# eBox_ACdetect2.net
KiCad netlist of a schematic drawn in Altium Designer
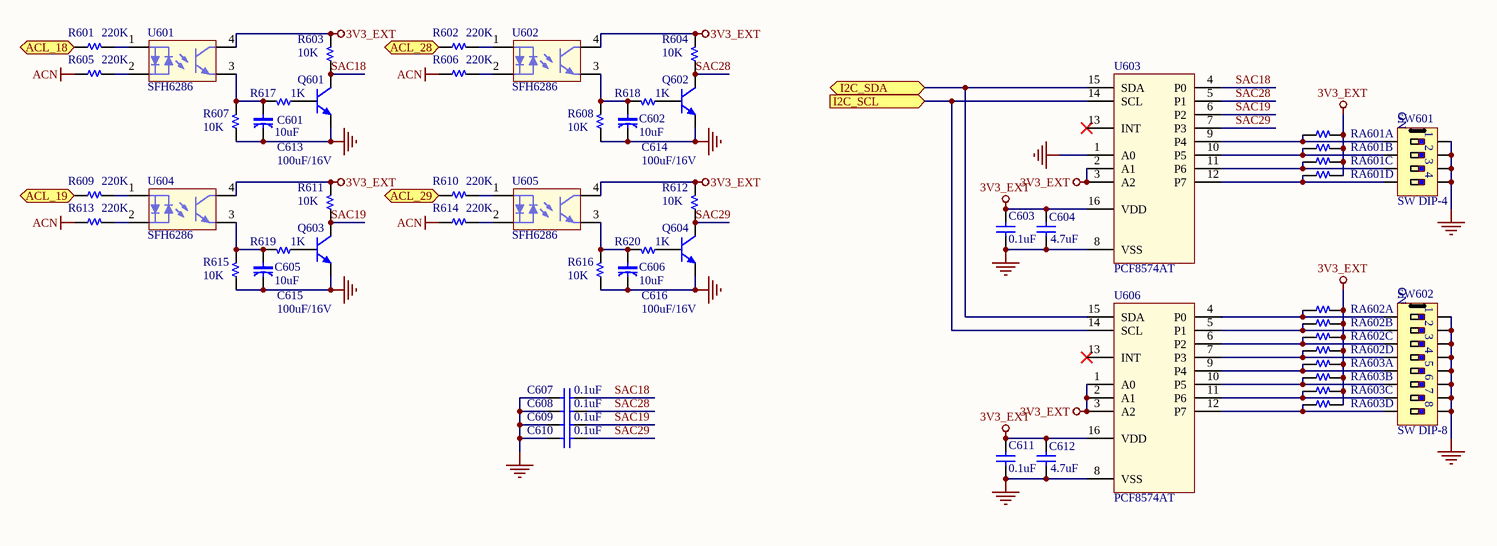
[diagram p0: eBox_ACdetect2.SchDoc]

(export (version "E")
  (design (tool "Eeschema 10.0.6"))
  (components
    (comp (ref "C601")
      (value "10uF")
      (footprint "C 0805")
      (description "CAP CER 0.1UF 50V X7R 0805")
      (libsource (lib "chipfc_altium_libs") (part "Capacitor NP"))
    )
    (comp (ref "C602")
      (value "10uF")
      (footprint "C 0805")
      (description "CAP CER 0.1UF 50V X7R 0805")
      (libsource (lib "chipfc_altium_libs") (part "Capacitor NP"))
    )
    (comp (ref "C603")
      (value "0.1uF")
      (footprint "C 0603")
      (description "CAP CER 0.1UF 50V X7R 0603")
      (libsource (lib "chipfc_altium_libs") (part "Capacitor NP"))
    )
    (comp (ref "C604")
      (value "4.7uF")
      (footprint "C 0603")
      (description "CAP CER 4.7UF 50V X7R 0603")
      (libsource (lib "chipfc_altium_libs") (part "Capacitor NP"))
    )
    (comp (ref "C605")
      (value "10uF")
      (footprint "C 0805")
      (description "CAP CER 0.1UF 50V X7R 0805")
      (libsource (lib "chipfc_altium_libs") (part "Capacitor NP"))
    )
    (comp (ref "C606")
      (value "10uF")
      (footprint "C 0805")
      (description "CAP CER 0.1UF 50V X7R 0805")
      (libsource (lib "chipfc_altium_libs") (part "Capacitor NP"))
    )
    (comp (ref "C607")
      (value "0.1uF")
      (footprint "C 0805")
      (description "CAP CER 0.1UF 50V X7R 0805")
      (libsource (lib "chipfc_altium_libs") (part "Capacitor NP"))
    )
    (comp (ref "C608")
      (value "0.1uF")
      (footprint "C 0805")
      (description "CAP CER 0.1UF 50V X7R 0805")
      (libsource (lib "chipfc_altium_libs") (part "Capacitor NP"))
    )
    (comp (ref "C609")
      (value "0.1uF")
      (footprint "C 0805")
      (description "CAP CER 0.1UF 50V X7R 0805")
      (libsource (lib "chipfc_altium_libs") (part "Capacitor NP"))
    )
    (comp (ref "C610")
      (value "0.1uF")
      (footprint "C 0805")
      (description "CAP CER 0.1UF 50V X7R 0805")
      (libsource (lib "chipfc_altium_libs") (part "Capacitor NP"))
    )
    (comp (ref "C611")
      (value "0.1uF")
      (footprint "C 0603")
      (description "CAP CER 0.1UF 50V X7R 0603")
      (libsource (lib "chipfc_altium_libs") (part "Capacitor NP"))
    )
    (comp (ref "C612")
      (value "4.7uF")
      (footprint "C 0603")
      (description "CAP CER 4.7UF 50V X7R 0603")
      (libsource (lib "chipfc_altium_libs") (part "Capacitor NP"))
    )
    (comp (ref "C613")
      (value "100uF/16V")
      (footprint "CYL/D.200/LS.75")
      (description "Capacitor pol")
      (libsource (lib "chipfc_altium_libs") (part "Capacitor"))
    )
    (comp (ref "C614")
      (value "100uF/16V")
      (footprint "CYL/D.200/LS.75")
      (description "Capacitor pol")
      (libsource (lib "chipfc_altium_libs") (part "Capacitor"))
    )
    (comp (ref "C615")
      (value "100uF/16V")
      (footprint "CYL/D.200/LS.75")
      (description "Capacitor pol")
      (libsource (lib "chipfc_altium_libs") (part "Capacitor"))
    )
    (comp (ref "C616")
      (value "100uF/16V")
      (footprint "CYL/D.200/LS.75")
      (description "Capacitor pol")
      (libsource (lib "chipfc_altium_libs") (part "Capacitor"))
    )
    (comp (ref "Q601")
      (value "MMBT3904LT1G")
      (footprint "SOT-23")
      (description "TRANS NPN 40V 0.2A SOT23")
      (libsource (lib "chipfc_altium_libs") (part "Transistor NPN"))
    )
    (comp (ref "Q602")
      (value "MMBT3904LT1G")
      (footprint "SOT-23")
      (description "TRANS NPN 40V 0.2A SOT23")
      (libsource (lib "chipfc_altium_libs") (part "Transistor NPN"))
    )
    (comp (ref "Q603")
      (value "MMBT3904LT1G")
      (footprint "SOT-23")
      (description "TRANS NPN 40V 0.2A SOT23")
      (libsource (lib "chipfc_altium_libs") (part "Transistor NPN"))
    )
    (comp (ref "Q604")
      (value "MMBT3904LT1G")
      (footprint "SOT-23")
      (description "TRANS NPN 40V 0.2A SOT23")
      (libsource (lib "chipfc_altium_libs") (part "Transistor NPN"))
    )
    (comp (ref "R601")
      (value "220K")
      (footprint "R 0805")
      (description "RES SMD 220K OHM 1% 1/8W 0805")
      (libsource (lib "chipfc_altium_libs") (part "Resistor"))
    )
    (comp (ref "R602")
      (value "220K")
      (footprint "R 0805")
      (description "RES SMD 220K OHM 1% 1/8W 0805")
      (libsource (lib "chipfc_altium_libs") (part "Resistor"))
    )
    (comp (ref "R603")
      (value "10K")
      (footprint "R 0805")
      (description "RES SMD 10K OHM 1% 1/8W 0805")
      (libsource (lib "chipfc_altium_libs") (part "Resistor"))
    )
    (comp (ref "R604")
      (value "10K")
      (footprint "R 0805")
      (description "RES SMD 10K OHM 1% 1/8W 0805")
      (libsource (lib "chipfc_altium_libs") (part "Resistor"))
    )
    (comp (ref "R605")
      (value "220K")
      (footprint "R 0805")
      (description "RES SMD 220K OHM 1% 1/8W 0805")
      (libsource (lib "chipfc_altium_libs") (part "Resistor"))
    )
    (comp (ref "R606")
      (value "220K")
      (footprint "R 0805")
      (description "RES SMD 220K OHM 1% 1/8W 0805")
      (libsource (lib "chipfc_altium_libs") (part "Resistor"))
    )
    (comp (ref "R607")
      (value "10K")
      (footprint "R 0805")
      (description "RES SMD 10K OHM 1% 1/8W 0805")
      (libsource (lib "chipfc_altium_libs") (part "Resistor"))
    )
    (comp (ref "R608")
      (value "10K")
      (footprint "R 0805")
      (description "RES SMD 10K OHM 1% 1/8W 0805")
      (libsource (lib "chipfc_altium_libs") (part "Resistor"))
    )
    (comp (ref "R609")
      (value "220K")
      (footprint "R 0805")
      (description "RES SMD 220K OHM 1% 1/8W 0805")
      (libsource (lib "chipfc_altium_libs") (part "Resistor"))
    )
    (comp (ref "R610")
      (value "220K")
      (footprint "R 0805")
      (description "RES SMD 220K OHM 1% 1/8W 0805")
      (libsource (lib "chipfc_altium_libs") (part "Resistor"))
    )
    (comp (ref "R611")
      (value "10K")
      (footprint "R 0805")
      (description "RES SMD 10K OHM 1% 1/8W 0805")
      (libsource (lib "chipfc_altium_libs") (part "Resistor"))
    )
    (comp (ref "R612")
      (value "10K")
      (footprint "R 0805")
      (description "RES SMD 10K OHM 1% 1/8W 0805")
      (libsource (lib "chipfc_altium_libs") (part "Resistor"))
    )
    (comp (ref "R613")
      (value "220K")
      (footprint "R 0805")
      (description "RES SMD 220K OHM 1% 1/8W 0805")
      (libsource (lib "chipfc_altium_libs") (part "Resistor"))
    )
    (comp (ref "R614")
      (value "220K")
      (footprint "R 0805")
      (description "RES SMD 220K OHM 1% 1/8W 0805")
      (libsource (lib "chipfc_altium_libs") (part "Resistor"))
    )
    (comp (ref "R615")
      (value "10K")
      (footprint "R 0805")
      (description "RES SMD 10K OHM 1% 1/8W 0805")
      (libsource (lib "chipfc_altium_libs") (part "Resistor"))
    )
    (comp (ref "R616")
      (value "10K")
      (footprint "R 0805")
      (description "RES SMD 10K OHM 1% 1/8W 0805")
      (libsource (lib "chipfc_altium_libs") (part "Resistor"))
    )
    (comp (ref "R617")
      (value "1K")
      (footprint "R 0805")
      (description "RES SMD 10K OHM 1% 1/8W 0805")
      (libsource (lib "chipfc_altium_libs") (part "Resistor"))
    )
    (comp (ref "R618")
      (value "1K")
      (footprint "R 0805")
      (description "RES SMD 10K OHM 1% 1/8W 0805")
      (libsource (lib "chipfc_altium_libs") (part "Resistor"))
    )
    (comp (ref "R619")
      (value "1K")
      (footprint "R 0805")
      (description "RES SMD 10K OHM 1% 1/8W 0805")
      (libsource (lib "chipfc_altium_libs") (part "Resistor"))
    )
    (comp (ref "R620")
      (value "1K")
      (footprint "R 0805")
      (description "RES SMD 10K OHM 1% 1/8W 0805")
      (libsource (lib "chipfc_altium_libs") (part "Resistor"))
    )
    (comp (ref "RA601")
      (value "10K")
      (footprint "RAx4 1206 (3216)")
      (libsource (lib "chipfc_altium_libs") (part "Resistor Array x4"))
    )
    (comp (ref "RA602")
      (value "10K")
      (footprint "RAx4 1206 (3216)")
      (libsource (lib "chipfc_altium_libs") (part "Resistor Array x4"))
    )
    (comp (ref "RA603")
      (value "10K")
      (footprint "RAx4 1206 (3216)")
      (libsource (lib "chipfc_altium_libs") (part "Resistor Array x4"))
    )
    (comp (ref "SW601")
      (value "SW DIP-4")
      (footprint "SW/DIP4")
      (libsource (lib "chipfc_altium_libs") (part "SW DIP-4"))
    )
    (comp (ref "SW602")
      (value "SW DIP-8")
      (footprint "SW/DIP8/300")
      (libsource (lib "chipfc_altium_libs") (part "SW DIP-8"))
    )
    (comp (ref "U601")
      (value "SFH6286")
      (footprint "SOP4 - SFH6286")
      (libsource (lib "chipfc_altium_libs") (part "SFH6286"))
    )
    (comp (ref "U602")
      (value "SFH6286")
      (footprint "SOP4 - SFH6286")
      (libsource (lib "chipfc_altium_libs") (part "SFH6286"))
    )
    (comp (ref "U603")
      (value "PCF8574AT")
      (footprint "SO16/PCF8574AT")
      (description "Remote 8-bit I/O expander for I2C-bus with interrupt")
      (fields (field (name "PART NO") "PCF8574AT/3"))
      (libsource (lib "chipfc_altium_libs") (part "PCF8574AT"))
    )
    (comp (ref "U604")
      (value "SFH6286")
      (footprint "SOP4 - SFH6286")
      (libsource (lib "chipfc_altium_libs") (part "SFH6286"))
    )
    (comp (ref "U605")
      (value "SFH6286")
      (footprint "SOP4 - SFH6286")
      (libsource (lib "chipfc_altium_libs") (part "SFH6286"))
    )
    (comp (ref "U606")
      (value "PCF8574AT")
      (footprint "SO16/PCF8574AT")
      (description "Remote 8-bit I/O expander for I2C-bus with interrupt")
      (fields (field (name "PART NO") "PCF8574AT/3"))
      (libsource (lib "chipfc_altium_libs") (part "PCF8574AT"))
    )
  )
  (nets
    (net (code "1") (name "/ACL_18") (class "Default")
      (node (ref "R601") (pin "1") (pinfunction "1_1") (pintype "passive"))
    )
    (net (code "2") (name "/ACL_19") (class "Default")
      (node (ref "R609") (pin "1") (pinfunction "1_1") (pintype "passive"))
    )
    (net (code "3") (name "/ACL_28") (class "Default")
      (node (ref "R602") (pin "1") (pinfunction "1_1") (pintype "passive"))
    )
    (net (code "4") (name "/ACL_29") (class "Default")
      (node (ref "R610") (pin "1") (pinfunction "1_1") (pintype "passive"))
    )
    (net (code "5") (name "/I2C_SCL") (class "Default")
      (node (ref "U603") (pin "14") (pinfunction "SCL_14") (pintype "passive"))
      (node (ref "U606") (pin "14") (pinfunction "SCL_14") (pintype "passive"))
    )
    (net (code "6") (name "/I2C_SDA") (class "Default")
      (node (ref "U603") (pin "15") (pinfunction "SDA_15") (pintype "passive"))
      (node (ref "U606") (pin "15") (pinfunction "SDA_15") (pintype "passive"))
    )
    (net (code "7") (name "/SAC18") (class "Default")
      (node (ref "C607") (pin "2") (pinfunction "2_2") (pintype "passive"))
      (node (ref "Q601") (pin "3") (pinfunction "C_3") (pintype "passive"))
      (node (ref "R603") (pin "1") (pinfunction "1_1") (pintype "passive"))
      (node (ref "U603") (pin "4") (pinfunction "P0_4") (pintype "passive"))
    )
    (net (code "8") (name "/SAC19") (class "Default")
      (node (ref "C609") (pin "2") (pinfunction "2_2") (pintype "passive"))
      (node (ref "Q603") (pin "3") (pinfunction "C_3") (pintype "passive"))
      (node (ref "R611") (pin "1") (pinfunction "1_1") (pintype "passive"))
      (node (ref "U603") (pin "6") (pinfunction "P2_6") (pintype "passive"))
    )
    (net (code "9") (name "/SAC28") (class "Default")
      (node (ref "C608") (pin "2") (pinfunction "2_2") (pintype "passive"))
      (node (ref "Q602") (pin "3") (pinfunction "C_3") (pintype "passive"))
      (node (ref "R604") (pin "1") (pinfunction "1_1") (pintype "passive"))
      (node (ref "U603") (pin "5") (pinfunction "P1_5") (pintype "passive"))
    )
    (net (code "10") (name "/SAC29") (class "Default")
      (node (ref "C610") (pin "2") (pinfunction "2_2") (pintype "passive"))
      (node (ref "Q604") (pin "3") (pinfunction "C_3") (pintype "passive"))
      (node (ref "R612") (pin "1") (pinfunction "1_1") (pintype "passive"))
      (node (ref "U603") (pin "7") (pinfunction "P3_7") (pintype "passive"))
    )
    (net (code "11") (name "3V3_EXT") (class "Default")
      (node (ref "C603") (pin "1") (pinfunction "1_1") (pintype "passive"))
      (node (ref "C604") (pin "1") (pinfunction "1_1") (pintype "passive"))
      (node (ref "C611") (pin "1") (pinfunction "1_1") (pintype "passive"))
      (node (ref "C612") (pin "1") (pinfunction "1_1") (pintype "passive"))
      (node (ref "R603") (pin "2") (pinfunction "2_2") (pintype "passive"))
      (node (ref "R604") (pin "2") (pinfunction "2_2") (pintype "passive"))
      (node (ref "R611") (pin "2") (pinfunction "2_2") (pintype "passive"))
      (node (ref "R612") (pin "2") (pinfunction "2_2") (pintype "passive"))
      (node (ref "RA601") (pin "5") (pinfunction "5_5") (pintype "passive"))
      (node (ref "RA601") (pin "6") (pinfunction "6_6") (pintype "passive"))
      (node (ref "RA601") (pin "7") (pinfunction "7_7") (pintype "passive"))
      (node (ref "RA601") (pin "8") (pinfunction "8_8") (pintype "passive"))
      (node (ref "RA602") (pin "5") (pinfunction "5_5") (pintype "passive"))
      (node (ref "RA602") (pin "6") (pinfunction "6_6") (pintype "passive"))
      (node (ref "RA602") (pin "7") (pinfunction "7_7") (pintype "passive"))
      (node (ref "RA602") (pin "8") (pinfunction "8_8") (pintype "passive"))
      (node (ref "RA603") (pin "5") (pinfunction "5_5") (pintype "passive"))
      (node (ref "RA603") (pin "6") (pinfunction "6_6") (pintype "passive"))
      (node (ref "RA603") (pin "7") (pinfunction "7_7") (pintype "passive"))
      (node (ref "RA603") (pin "8") (pinfunction "8_8") (pintype "passive"))
      (node (ref "U601") (pin "4") (pinfunction "C_4") (pintype "passive"))
      (node (ref "U602") (pin "4") (pinfunction "C_4") (pintype "passive"))
      (node (ref "U603") (pin "16") (pinfunction "VDD_16") (pintype "passive"))
      (node (ref "U603") (pin "2") (pinfunction "A1_2") (pintype "passive"))
      (node (ref "U603") (pin "3") (pinfunction "A2_3") (pintype "passive"))
      (node (ref "U604") (pin "4") (pinfunction "C_4") (pintype "passive"))
      (node (ref "U605") (pin "4") (pinfunction "C_4") (pintype "passive"))
      (node (ref "U606") (pin "1") (pinfunction "A0_1") (pintype "passive"))
      (node (ref "U606") (pin "16") (pinfunction "VDD_16") (pintype "passive"))
      (node (ref "U606") (pin "2") (pinfunction "A1_2") (pintype "passive"))
      (node (ref "U606") (pin "3") (pinfunction "A2_3") (pintype "passive"))
    )
    (net (code "12") (name "ACN") (class "Default")
      (node (ref "R605") (pin "1") (pinfunction "1_1") (pintype "passive"))
      (node (ref "R606") (pin "1") (pinfunction "1_1") (pintype "passive"))
      (node (ref "R613") (pin "1") (pinfunction "1_1") (pintype "passive"))
      (node (ref "R614") (pin "1") (pinfunction "1_1") (pintype "passive"))
    )
    (net (code "13") (name "GND") (class "Default")
      (node (ref "C601") (pin "2") (pinfunction "2_2") (pintype "passive"))
      (node (ref "C602") (pin "2") (pinfunction "2_2") (pintype "passive"))
      (node (ref "C603") (pin "2") (pinfunction "2_2") (pintype "passive"))
      (node (ref "C604") (pin "2") (pinfunction "2_2") (pintype "passive"))
      (node (ref "C605") (pin "2") (pinfunction "2_2") (pintype "passive"))
      (node (ref "C606") (pin "2") (pinfunction "2_2") (pintype "passive"))
      (node (ref "C607") (pin "1") (pinfunction "1_1") (pintype "passive"))
      (node (ref "C608") (pin "1") (pinfunction "1_1") (pintype "passive"))
      (node (ref "C609") (pin "1") (pinfunction "1_1") (pintype "passive"))
      (node (ref "C610") (pin "1") (pinfunction "1_1") (pintype "passive"))
      (node (ref "C611") (pin "2") (pinfunction "2_2") (pintype "passive"))
      (node (ref "C612") (pin "2") (pinfunction "2_2") (pintype "passive"))
      (node (ref "C613") (pin "2") (pinfunction "2_2") (pintype "passive"))
      (node (ref "C614") (pin "2") (pinfunction "2_2") (pintype "passive"))
      (node (ref "C615") (pin "2") (pinfunction "2_2") (pintype "passive"))
      (node (ref "C616") (pin "2") (pinfunction "2_2") (pintype "passive"))
      (node (ref "Q601") (pin "2") (pinfunction "E_2") (pintype "passive"))
      (node (ref "Q602") (pin "2") (pinfunction "E_2") (pintype "passive"))
      (node (ref "Q603") (pin "2") (pinfunction "E_2") (pintype "passive"))
      (node (ref "Q604") (pin "2") (pinfunction "E_2") (pintype "passive"))
      (node (ref "R607") (pin "1") (pinfunction "1_1") (pintype "passive"))
      (node (ref "R608") (pin "1") (pinfunction "1_1") (pintype "passive"))
      (node (ref "R615") (pin "1") (pinfunction "1_1") (pintype "passive"))
      (node (ref "R616") (pin "1") (pinfunction "1_1") (pintype "passive"))
      (node (ref "SW601") (pin "1") (pinfunction "1_1") (pintype "passive"))
      (node (ref "SW601") (pin "2") (pinfunction "2_2") (pintype "passive"))
      (node (ref "SW601") (pin "3") (pinfunction "3_3") (pintype "passive"))
      (node (ref "SW601") (pin "4") (pinfunction "4_4") (pintype "passive"))
      (node (ref "SW602") (pin "1") (pinfunction "1_1") (pintype "passive"))
      (node (ref "SW602") (pin "2") (pinfunction "2_2") (pintype "passive"))
      (node (ref "SW602") (pin "3") (pinfunction "3_3") (pintype "passive"))
      (node (ref "SW602") (pin "4") (pinfunction "4_4") (pintype "passive"))
      (node (ref "SW602") (pin "5") (pinfunction "5_5") (pintype "passive"))
      (node (ref "SW602") (pin "6") (pinfunction "6_6") (pintype "passive"))
      (node (ref "SW602") (pin "7") (pinfunction "7_7") (pintype "passive"))
      (node (ref "SW602") (pin "8") (pinfunction "8_8") (pintype "passive"))
      (node (ref "U603") (pin "1") (pinfunction "A0_1") (pintype "passive"))
      (node (ref "U603") (pin "8") (pinfunction "VSS_8") (pintype "passive"))
      (node (ref "U606") (pin "8") (pinfunction "VSS_8") (pintype "passive"))
    )
    (net (code "14") (name "Net-(Q601-B)") (class "Default")
      (node (ref "Q601") (pin "1") (pinfunction "B_1") (pintype "passive"))
      (node (ref "R617") (pin "1") (pinfunction "1_1") (pintype "passive"))
    )
    (net (code "15") (name "Net-(Q602-B)") (class "Default")
      (node (ref "Q602") (pin "1") (pinfunction "B_1") (pintype "passive"))
      (node (ref "R618") (pin "1") (pinfunction "1_1") (pintype "passive"))
    )
    (net (code "16") (name "Net-(Q603-B)") (class "Default")
      (node (ref "Q603") (pin "1") (pinfunction "B_1") (pintype "passive"))
      (node (ref "R619") (pin "1") (pinfunction "1_1") (pintype "passive"))
    )
    (net (code "17") (name "Net-(Q604-B)") (class "Default")
      (node (ref "Q604") (pin "1") (pinfunction "B_1") (pintype "passive"))
      (node (ref "R620") (pin "1") (pinfunction "1_1") (pintype "passive"))
    )
    (net (code "18") (name "Net-(U601-A{slash}C)") (class "Default")
      (node (ref "R601") (pin "2") (pinfunction "2_2") (pintype "passive"))
      (node (ref "U601") (pin "1") (pinfunction "A/C_1") (pintype "passive"))
    )
    (net (code "19") (name "Net-(U601-C{slash}A)") (class "Default")
      (node (ref "R605") (pin "2") (pinfunction "2_2") (pintype "passive"))
      (node (ref "U601") (pin "2") (pinfunction "C/A_2") (pintype "passive"))
    )
    (net (code "20") (name "Net-(U601-E)") (class "Default")
      (node (ref "C601") (pin "1") (pinfunction "1_1") (pintype "passive"))
      (node (ref "C613") (pin "1") (pinfunction "1_1") (pintype "passive"))
      (node (ref "R607") (pin "2") (pinfunction "2_2") (pintype "passive"))
      (node (ref "R617") (pin "2") (pinfunction "2_2") (pintype "passive"))
      (node (ref "U601") (pin "3") (pinfunction "E_3") (pintype "passive"))
    )
    (net (code "21") (name "Net-(U602-A{slash}C)") (class "Default")
      (node (ref "R602") (pin "2") (pinfunction "2_2") (pintype "passive"))
      (node (ref "U602") (pin "1") (pinfunction "A/C_1") (pintype "passive"))
    )
    (net (code "22") (name "Net-(U602-C{slash}A)") (class "Default")
      (node (ref "R606") (pin "2") (pinfunction "2_2") (pintype "passive"))
      (node (ref "U602") (pin "2") (pinfunction "C/A_2") (pintype "passive"))
    )
    (net (code "23") (name "Net-(U602-E)") (class "Default")
      (node (ref "C602") (pin "1") (pinfunction "1_1") (pintype "passive"))
      (node (ref "C614") (pin "1") (pinfunction "1_1") (pintype "passive"))
      (node (ref "R608") (pin "2") (pinfunction "2_2") (pintype "passive"))
      (node (ref "R618") (pin "2") (pinfunction "2_2") (pintype "passive"))
      (node (ref "U602") (pin "3") (pinfunction "E_3") (pintype "passive"))
    )
    (net (code "24") (name "Net-(U603-P4)") (class "Default")
      (node (ref "RA601") (pin "1") (pinfunction "1_1") (pintype "passive"))
      (node (ref "SW601") (pin "8") (pinfunction "8_8") (pintype "passive"))
      (node (ref "U603") (pin "9") (pinfunction "P4_9") (pintype "passive"))
    )
    (net (code "25") (name "Net-(U603-P5)") (class "Default")
      (node (ref "RA601") (pin "2") (pinfunction "2_2") (pintype "passive"))
      (node (ref "SW601") (pin "7") (pinfunction "7_7") (pintype "passive"))
      (node (ref "U603") (pin "10") (pinfunction "P5_10") (pintype "passive"))
    )
    (net (code "26") (name "Net-(U603-P6)") (class "Default")
      (node (ref "RA601") (pin "3") (pinfunction "3_3") (pintype "passive"))
      (node (ref "SW601") (pin "6") (pinfunction "6_6") (pintype "passive"))
      (node (ref "U603") (pin "11") (pinfunction "P6_11") (pintype "passive"))
    )
    (net (code "27") (name "Net-(U603-P7)") (class "Default")
      (node (ref "RA601") (pin "4") (pinfunction "4_4") (pintype "passive"))
      (node (ref "SW601") (pin "5") (pinfunction "5_5") (pintype "passive"))
      (node (ref "U603") (pin "12") (pinfunction "P7_12") (pintype "passive"))
    )
    (net (code "28") (name "Net-(U604-A{slash}C)") (class "Default")
      (node (ref "R609") (pin "2") (pinfunction "2_2") (pintype "passive"))
      (node (ref "U604") (pin "1") (pinfunction "A/C_1") (pintype "passive"))
    )
    (net (code "29") (name "Net-(U604-C{slash}A)") (class "Default")
      (node (ref "R613") (pin "2") (pinfunction "2_2") (pintype "passive"))
      (node (ref "U604") (pin "2") (pinfunction "C/A_2") (pintype "passive"))
    )
    (net (code "30") (name "Net-(U604-E)") (class "Default")
      (node (ref "C605") (pin "1") (pinfunction "1_1") (pintype "passive"))
      (node (ref "C615") (pin "1") (pinfunction "1_1") (pintype "passive"))
      (node (ref "R615") (pin "2") (pinfunction "2_2") (pintype "passive"))
      (node (ref "R619") (pin "2") (pinfunction "2_2") (pintype "passive"))
      (node (ref "U604") (pin "3") (pinfunction "E_3") (pintype "passive"))
    )
    (net (code "31") (name "Net-(U605-A{slash}C)") (class "Default")
      (node (ref "R610") (pin "2") (pinfunction "2_2") (pintype "passive"))
      (node (ref "U605") (pin "1") (pinfunction "A/C_1") (pintype "passive"))
    )
    (net (code "32") (name "Net-(U605-C{slash}A)") (class "Default")
      (node (ref "R614") (pin "2") (pinfunction "2_2") (pintype "passive"))
      (node (ref "U605") (pin "2") (pinfunction "C/A_2") (pintype "passive"))
    )
    (net (code "33") (name "Net-(U605-E)") (class "Default")
      (node (ref "C606") (pin "1") (pinfunction "1_1") (pintype "passive"))
      (node (ref "C616") (pin "1") (pinfunction "1_1") (pintype "passive"))
      (node (ref "R616") (pin "2") (pinfunction "2_2") (pintype "passive"))
      (node (ref "R620") (pin "2") (pinfunction "2_2") (pintype "passive"))
      (node (ref "U605") (pin "3") (pinfunction "E_3") (pintype "passive"))
    )
    (net (code "34") (name "Net-(U606-P0)") (class "Default")
      (node (ref "RA602") (pin "1") (pinfunction "1_1") (pintype "passive"))
      (node (ref "SW602") (pin "16") (pinfunction "16_16") (pintype "passive"))
      (node (ref "U606") (pin "4") (pinfunction "P0_4") (pintype "passive"))
    )
    (net (code "35") (name "Net-(U606-P1)") (class "Default")
      (node (ref "RA602") (pin "2") (pinfunction "2_2") (pintype "passive"))
      (node (ref "SW602") (pin "15") (pinfunction "15_15") (pintype "passive"))
      (node (ref "U606") (pin "5") (pinfunction "P1_5") (pintype "passive"))
    )
    (net (code "36") (name "Net-(U606-P2)") (class "Default")
      (node (ref "RA602") (pin "3") (pinfunction "3_3") (pintype "passive"))
      (node (ref "SW602") (pin "14") (pinfunction "14_14") (pintype "passive"))
      (node (ref "U606") (pin "6") (pinfunction "P2_6") (pintype "passive"))
    )
    (net (code "37") (name "Net-(U606-P3)") (class "Default")
      (node (ref "RA602") (pin "4") (pinfunction "4_4") (pintype "passive"))
      (node (ref "SW602") (pin "13") (pinfunction "13_13") (pintype "passive"))
      (node (ref "U606") (pin "7") (pinfunction "P3_7") (pintype "passive"))
    )
    (net (code "38") (name "Net-(U606-P4)") (class "Default")
      (node (ref "RA603") (pin "1") (pinfunction "1_1") (pintype "passive"))
      (node (ref "SW602") (pin "12") (pinfunction "12_12") (pintype "passive"))
      (node (ref "U606") (pin "9") (pinfunction "P4_9") (pintype "passive"))
    )
    (net (code "39") (name "Net-(U606-P5)") (class "Default")
      (node (ref "RA603") (pin "2") (pinfunction "2_2") (pintype "passive"))
      (node (ref "SW602") (pin "11") (pinfunction "11_11") (pintype "passive"))
      (node (ref "U606") (pin "10") (pinfunction "P5_10") (pintype "passive"))
    )
    (net (code "40") (name "Net-(U606-P6)") (class "Default")
      (node (ref "RA603") (pin "3") (pinfunction "3_3") (pintype "passive"))
      (node (ref "SW602") (pin "10") (pinfunction "10_10") (pintype "passive"))
      (node (ref "U606") (pin "11") (pinfunction "P6_11") (pintype "passive"))
    )
    (net (code "41") (name "Net-(U606-P7)") (class "Default")
      (node (ref "RA603") (pin "4") (pinfunction "4_4") (pintype "passive"))
      (node (ref "SW602") (pin "9") (pinfunction "9_9") (pintype "passive"))
      (node (ref "U606") (pin "12") (pinfunction "P7_12") (pintype "passive"))
    )
    (net (code "42") (name "unconnected-(U603-INT-Pad13)") (class "Default")
      (node (ref "U603") (pin "13") (pinfunction "INT_13") (pintype "passive+no_connect"))
    )
    (net (code "43") (name "unconnected-(U606-INT-Pad13)") (class "Default")
      (node (ref "U606") (pin "13") (pinfunction "INT_13") (pintype "passive+no_connect"))
    )
  )
)
